# PT2258-S_Breakout.net
KiCad netlist of a schematic drawn in EAGLE
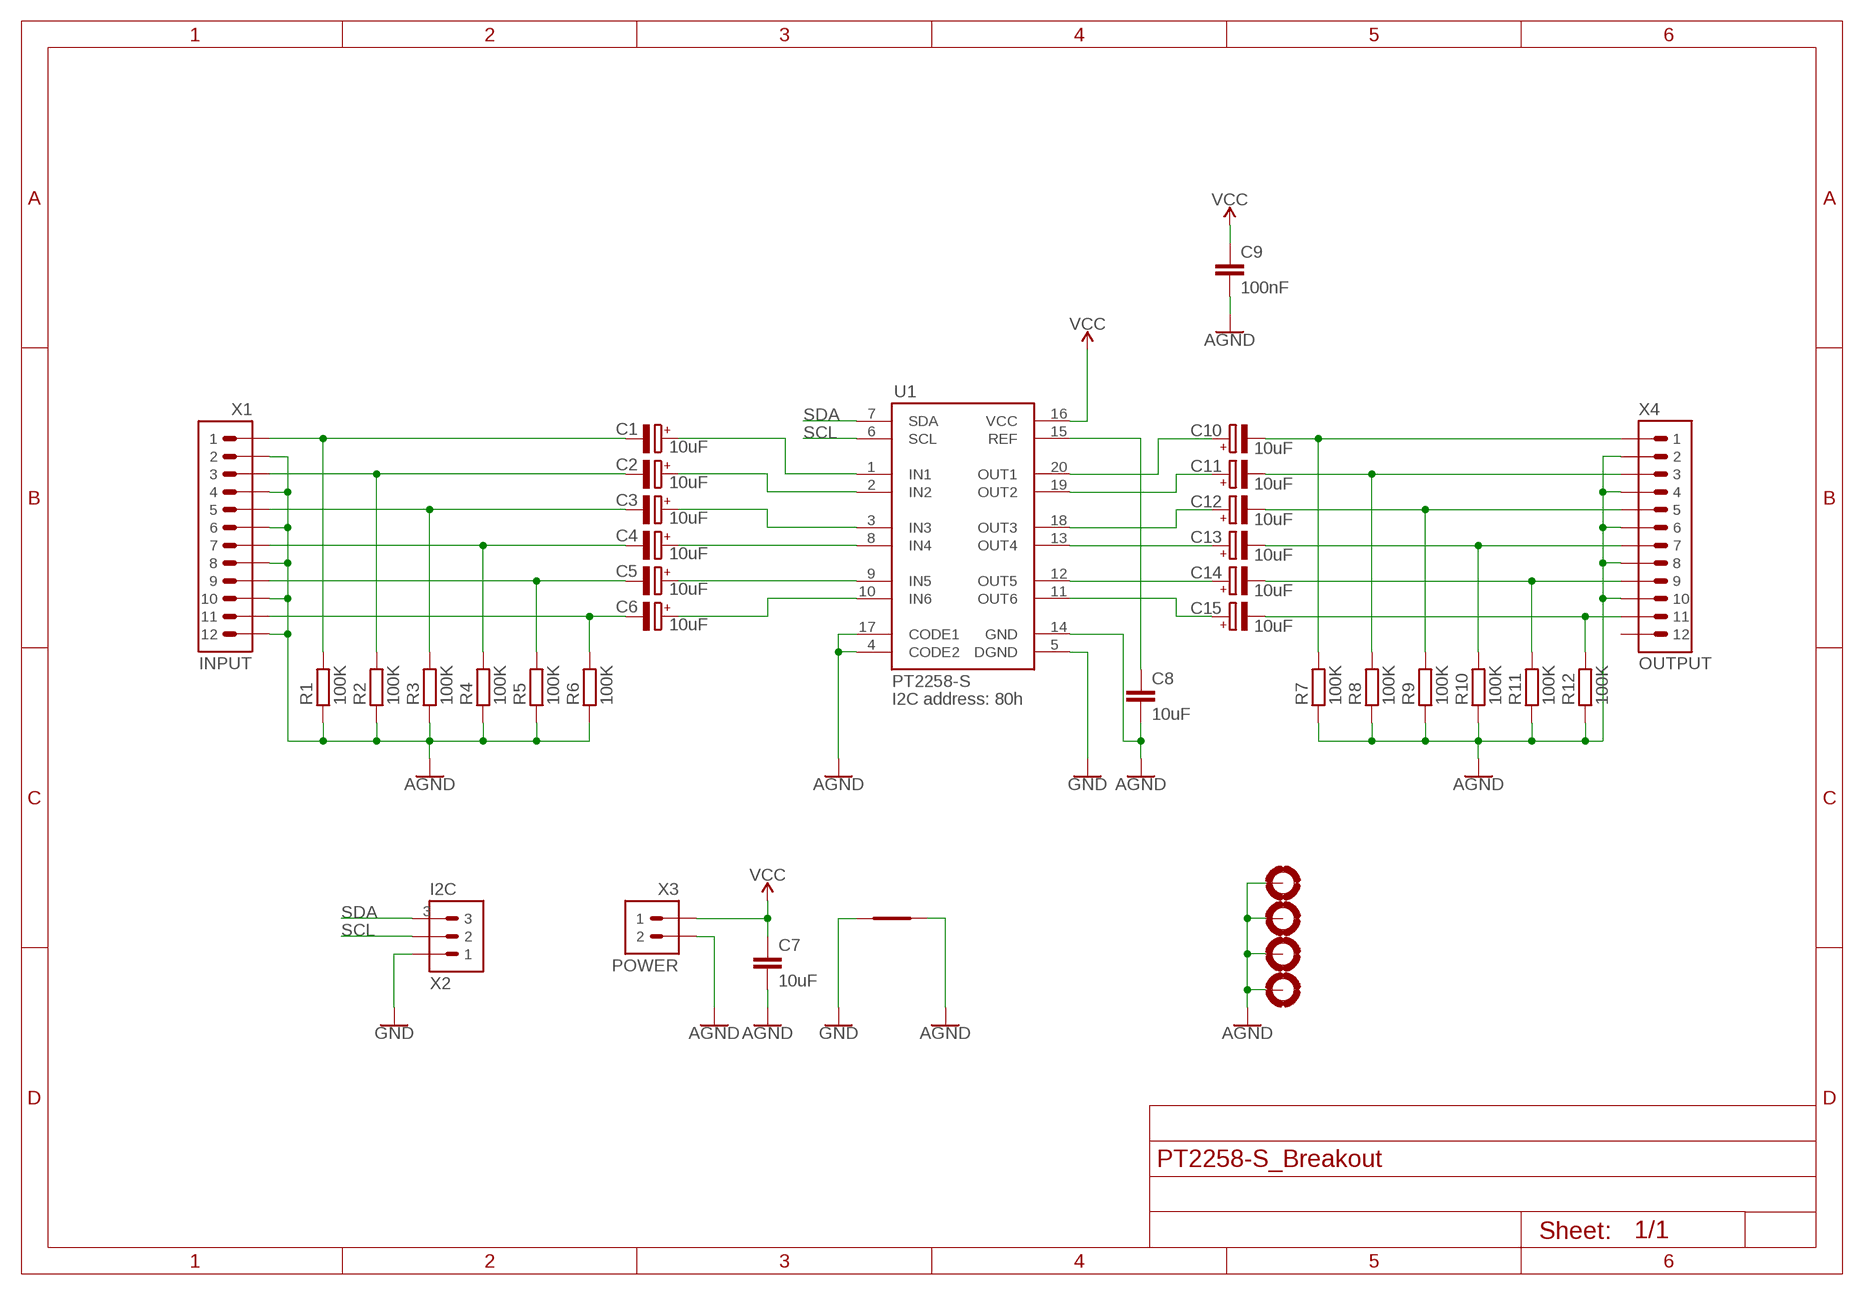
[diagram p0: schematic, sheet 1]

(export (version "E")
  (design (tool "Eeschema 10.0.6"))
  (components
    (comp (ref "C1")
      (value "10uF")
      (footprint "eagle-import:ROQANG-RVT0405")
      (libsource (lib "eagle-import") (part "CAP-POL-ALUMROQANG-RVT0405"))
    )
    (comp (ref "C2")
      (value "10uF")
      (footprint "eagle-import:ROQANG-RVT0405")
      (libsource (lib "eagle-import") (part "CAP-POL-ALUMROQANG-RVT0405"))
    )
    (comp (ref "C3")
      (value "10uF")
      (footprint "eagle-import:ROQANG-RVT0405")
      (libsource (lib "eagle-import") (part "CAP-POL-ALUMROQANG-RVT0405"))
    )
    (comp (ref "C4")
      (value "10uF")
      (footprint "eagle-import:ROQANG-RVT0405")
      (libsource (lib "eagle-import") (part "CAP-POL-ALUMROQANG-RVT0405"))
    )
    (comp (ref "C5")
      (value "10uF")
      (footprint "eagle-import:ROQANG-RVT0405")
      (libsource (lib "eagle-import") (part "CAP-POL-ALUMROQANG-RVT0405"))
    )
    (comp (ref "C6")
      (value "10uF")
      (footprint "eagle-import:ROQANG-RVT0405")
      (libsource (lib "eagle-import") (part "CAP-POL-ALUMROQANG-RVT0405"))
    )
    (comp (ref "C7")
      (value "10uF")
      (footprint "eagle-import:C0603")
      (libsource (lib "eagle-import") (part "CAPC0603"))
    )
    (comp (ref "C8")
      (value "10uF")
      (footprint "eagle-import:C0603")
      (libsource (lib "eagle-import") (part "CAPC0603"))
    )
    (comp (ref "C9")
      (value "100nF")
      (footprint "eagle-import:C0603")
      (libsource (lib "eagle-import") (part "CAPC0603"))
    )
    (comp (ref "C10")
      (value "10uF")
      (footprint "eagle-import:ROQANG-RVT0405")
      (libsource (lib "eagle-import") (part "CAP-POL-ALUMROQANG-RVT0405"))
    )
    (comp (ref "C11")
      (value "10uF")
      (footprint "eagle-import:ROQANG-RVT0405")
      (libsource (lib "eagle-import") (part "CAP-POL-ALUMROQANG-RVT0405"))
    )
    (comp (ref "C12")
      (value "10uF")
      (footprint "eagle-import:ROQANG-RVT0405")
      (libsource (lib "eagle-import") (part "CAP-POL-ALUMROQANG-RVT0405"))
    )
    (comp (ref "C13")
      (value "10uF")
      (footprint "eagle-import:ROQANG-RVT0405")
      (libsource (lib "eagle-import") (part "CAP-POL-ALUMROQANG-RVT0405"))
    )
    (comp (ref "C14")
      (value "10uF")
      (footprint "eagle-import:ROQANG-RVT0405")
      (libsource (lib "eagle-import") (part "CAP-POL-ALUMROQANG-RVT0405"))
    )
    (comp (ref "C15")
      (value "10uF")
      (footprint "eagle-import:ROQANG-RVT0405")
      (libsource (lib "eagle-import") (part "CAP-POL-ALUMROQANG-RVT0405"))
    )
    (comp (ref "H1")
      (value "MOUNTHOLE-PAD3.2")
      (footprint "eagle-import:3.2-PAD")
      (libsource (lib "eagle-import") (part "MOUNTHOLE-PAD3.2"))
    )
    (comp (ref "H2")
      (value "MOUNTHOLE-PAD3.2")
      (footprint "eagle-import:3.2-PAD")
      (libsource (lib "eagle-import") (part "MOUNTHOLE-PAD3.2"))
    )
    (comp (ref "H3")
      (value "MOUNTHOLE-PAD3.2")
      (footprint "eagle-import:3.2-PAD")
      (libsource (lib "eagle-import") (part "MOUNTHOLE-PAD3.2"))
    )
    (comp (ref "H4")
      (value "MOUNTHOLE-PAD3.2")
      (footprint "eagle-import:3.2-PAD")
      (libsource (lib "eagle-import") (part "MOUNTHOLE-PAD3.2"))
    )
    (comp (ref "R1")
      (value "100K")
      (footprint "eagle-import:R0603")
      (libsource (lib "eagle-import") (part "RESISTOR0603"))
    )
    (comp (ref "R2")
      (value "100K")
      (footprint "eagle-import:R0603")
      (libsource (lib "eagle-import") (part "RESISTOR0603"))
    )
    (comp (ref "R3")
      (value "100K")
      (footprint "eagle-import:R0603")
      (libsource (lib "eagle-import") (part "RESISTOR0603"))
    )
    (comp (ref "R4")
      (value "100K")
      (footprint "eagle-import:R0603")
      (libsource (lib "eagle-import") (part "RESISTOR0603"))
    )
    (comp (ref "R5")
      (value "100K")
      (footprint "eagle-import:R0603")
      (libsource (lib "eagle-import") (part "RESISTOR0603"))
    )
    (comp (ref "R6")
      (value "100K")
      (footprint "eagle-import:R0603")
      (libsource (lib "eagle-import") (part "RESISTOR0603"))
    )
    (comp (ref "R7")
      (value "100K")
      (footprint "eagle-import:R0603")
      (libsource (lib "eagle-import") (part "RESISTOR0603"))
    )
    (comp (ref "R8")
      (value "100K")
      (footprint "eagle-import:R0603")
      (libsource (lib "eagle-import") (part "RESISTOR0603"))
    )
    (comp (ref "R9")
      (value "100K")
      (footprint "eagle-import:R0603")
      (libsource (lib "eagle-import") (part "RESISTOR0603"))
    )
    (comp (ref "R10")
      (value "100K")
      (footprint "eagle-import:R0603")
      (libsource (lib "eagle-import") (part "RESISTOR0603"))
    )
    (comp (ref "R11")
      (value "100K")
      (footprint "eagle-import:R0603")
      (libsource (lib "eagle-import") (part "RESISTOR0603"))
    )
    (comp (ref "R12")
      (value "100K")
      (footprint "eagle-import:R0603")
      (libsource (lib "eagle-import") (part "RESISTOR0603"))
    )
    (comp (ref "SH1")
      (value "SHORT-SMD-06096")
      (footprint "eagle-import:SHORT-SMD-06096")
      (libsource (lib "eagle-import") (part "SHORT-SMD-06096"))
    )
    (comp (ref "U1")
      (value "PT2258-S")
      (footprint "eagle-import:SOP-20-300")
      (libsource (lib "eagle-import") (part "PT2258-S"))
    )
    (comp (ref "X1")
      (value "INPUT")
      (footprint "eagle-import:1X12-2.54")
      (libsource (lib "eagle-import") (part "HEADER-1X12-2.54"))
    )
    (comp (ref "X2")
      (value "I2C")
      (footprint "eagle-import:1X03P-2.54")
      (libsource (lib "eagle-import") (part "HEADER-1X03-2.54P"))
    )
    (comp (ref "X3")
      (value "POWER")
      (footprint "eagle-import:1X02P-2.54")
      (libsource (lib "eagle-import") (part "HEADER-1X02-2.54POL"))
    )
    (comp (ref "X4")
      (value "OUTPUT")
      (footprint "eagle-import:1X12-2.54")
      (libsource (lib "eagle-import") (part "HEADER-1X12-2.54"))
    )
  )
  (nets
    (net (code "1") (name "/SCL") (class "Default")
      (node (ref "U1") (pin "6") (pinfunction "SCL_6") (pintype "bidirectional"))
      (node (ref "X2") (pin "2") (pinfunction "2_2") (pintype "passive"))
    )
    (net (code "2") (name "/SDA") (class "Default")
      (node (ref "U1") (pin "7") (pinfunction "SDA_7") (pintype "bidirectional"))
      (node (ref "X2") (pin "3") (pinfunction "3_3") (pintype "passive"))
    )
    (net (code "3") (name "AGND") (class "Default")
      (node (ref "C7") (pin "2") (pinfunction "2_2") (pintype "passive"))
      (node (ref "C8") (pin "2") (pinfunction "2_2") (pintype "passive"))
      (node (ref "C9") (pin "2") (pinfunction "2_2") (pintype "passive"))
      (node (ref "H1") (pin "B3,2") (pinfunction "MOUNT_B3,2") (pintype "passive"))
      (node (ref "H2") (pin "B3,2") (pinfunction "MOUNT_B3,2") (pintype "passive"))
      (node (ref "H3") (pin "B3,2") (pinfunction "MOUNT_B3,2") (pintype "passive"))
      (node (ref "H4") (pin "B3,2") (pinfunction "MOUNT_B3,2") (pintype "passive"))
      (node (ref "R1") (pin "1") (pinfunction "1_1") (pintype "passive"))
      (node (ref "R10") (pin "1") (pinfunction "1_1") (pintype "passive"))
      (node (ref "R11") (pin "1") (pinfunction "1_1") (pintype "passive"))
      (node (ref "R12") (pin "1") (pinfunction "1_1") (pintype "passive"))
      (node (ref "R2") (pin "1") (pinfunction "1_1") (pintype "passive"))
      (node (ref "R3") (pin "1") (pinfunction "1_1") (pintype "passive"))
      (node (ref "R4") (pin "1") (pinfunction "1_1") (pintype "passive"))
      (node (ref "R5") (pin "1") (pinfunction "1_1") (pintype "passive"))
      (node (ref "R6") (pin "1") (pinfunction "1_1") (pintype "passive"))
      (node (ref "R7") (pin "1") (pinfunction "1_1") (pintype "passive"))
      (node (ref "R8") (pin "1") (pinfunction "1_1") (pintype "passive"))
      (node (ref "R9") (pin "1") (pinfunction "1_1") (pintype "passive"))
      (node (ref "SH1") (pin "2") (pinfunction "P$2_2") (pintype "bidirectional"))
      (node (ref "U1") (pin "14") (pinfunction "GND_14") (pintype "bidirectional"))
      (node (ref "U1") (pin "17") (pinfunction "CODE1_17") (pintype "bidirectional"))
      (node (ref "U1") (pin "4") (pinfunction "CODE2_4") (pintype "bidirectional"))
      (node (ref "X1") (pin "10") (pinfunction "10_10") (pintype "bidirectional"))
      (node (ref "X1") (pin "12") (pinfunction "12_12") (pintype "bidirectional"))
      (node (ref "X1") (pin "2") (pinfunction "2_2") (pintype "passive"))
      (node (ref "X1") (pin "4") (pinfunction "4_4") (pintype "passive"))
      (node (ref "X1") (pin "6") (pinfunction "6_6") (pintype "passive"))
      (node (ref "X1") (pin "8") (pinfunction "8_8") (pintype "bidirectional"))
      (node (ref "X3") (pin "2") (pinfunction "2_2") (pintype "passive"))
      (node (ref "X4") (pin "10") (pinfunction "10_10") (pintype "bidirectional"))
      (node (ref "X4") (pin "2") (pinfunction "2_2") (pintype "passive"))
      (node (ref "X4") (pin "4") (pinfunction "4_4") (pintype "passive"))
      (node (ref "X4") (pin "6") (pinfunction "6_6") (pintype "passive"))
      (node (ref "X4") (pin "8") (pinfunction "8_8") (pintype "bidirectional"))
    )
    (net (code "4") (name "GND") (class "Default")
      (node (ref "SH1") (pin "1") (pinfunction "P$1_1") (pintype "bidirectional"))
      (node (ref "U1") (pin "5") (pinfunction "DGND_5") (pintype "bidirectional"))
      (node (ref "X2") (pin "1") (pinfunction "1_1") (pintype "passive"))
    )
    (net (code "5") (name "Net-(C1-Pad-)") (class "Default")
      (node (ref "C1") (pin "-") (pinfunction "-_-") (pintype "passive"))
      (node (ref "R1") (pin "2") (pinfunction "2_2") (pintype "passive"))
      (node (ref "X1") (pin "1") (pinfunction "1_1") (pintype "passive"))
    )
    (net (code "6") (name "Net-(C2-Pad-)") (class "Default")
      (node (ref "C2") (pin "-") (pinfunction "-_-") (pintype "passive"))
      (node (ref "R2") (pin "2") (pinfunction "2_2") (pintype "passive"))
      (node (ref "X1") (pin "3") (pinfunction "3_3") (pintype "passive"))
    )
    (net (code "7") (name "Net-(C3-Pad-)") (class "Default")
      (node (ref "C3") (pin "-") (pinfunction "-_-") (pintype "passive"))
      (node (ref "R3") (pin "2") (pinfunction "2_2") (pintype "passive"))
      (node (ref "X1") (pin "5") (pinfunction "5_5") (pintype "passive"))
    )
    (net (code "8") (name "Net-(C4-Pad-)") (class "Default")
      (node (ref "C4") (pin "-") (pinfunction "-_-") (pintype "passive"))
      (node (ref "R4") (pin "2") (pinfunction "2_2") (pintype "passive"))
      (node (ref "X1") (pin "7") (pinfunction "7_7") (pintype "passive"))
    )
    (net (code "9") (name "Net-(C5-Pad-)") (class "Default")
      (node (ref "C5") (pin "-") (pinfunction "-_-") (pintype "passive"))
      (node (ref "R5") (pin "2") (pinfunction "2_2") (pintype "passive"))
      (node (ref "X1") (pin "9") (pinfunction "9_9") (pintype "bidirectional"))
    )
    (net (code "10") (name "Net-(C6-Pad-)") (class "Default")
      (node (ref "C6") (pin "-") (pinfunction "-_-") (pintype "passive"))
      (node (ref "R6") (pin "2") (pinfunction "2_2") (pintype "passive"))
      (node (ref "X1") (pin "11") (pinfunction "11_11") (pintype "bidirectional"))
    )
    (net (code "11") (name "Net-(C10-Pad-)") (class "Default")
      (node (ref "C10") (pin "-") (pinfunction "-_-") (pintype "passive"))
      (node (ref "R7") (pin "2") (pinfunction "2_2") (pintype "passive"))
      (node (ref "X4") (pin "1") (pinfunction "1_1") (pintype "passive"))
    )
    (net (code "12") (name "Net-(C11-Pad-)") (class "Default")
      (node (ref "C11") (pin "-") (pinfunction "-_-") (pintype "passive"))
      (node (ref "R8") (pin "2") (pinfunction "2_2") (pintype "passive"))
      (node (ref "X4") (pin "3") (pinfunction "3_3") (pintype "passive"))
    )
    (net (code "13") (name "Net-(C12-Pad-)") (class "Default")
      (node (ref "C12") (pin "-") (pinfunction "-_-") (pintype "passive"))
      (node (ref "R9") (pin "2") (pinfunction "2_2") (pintype "passive"))
      (node (ref "X4") (pin "5") (pinfunction "5_5") (pintype "passive"))
    )
    (net (code "14") (name "Net-(C13-Pad-)") (class "Default")
      (node (ref "C13") (pin "-") (pinfunction "-_-") (pintype "passive"))
      (node (ref "R10") (pin "2") (pinfunction "2_2") (pintype "passive"))
      (node (ref "X4") (pin "7") (pinfunction "7_7") (pintype "passive"))
    )
    (net (code "15") (name "Net-(C14-Pad-)") (class "Default")
      (node (ref "C14") (pin "-") (pinfunction "-_-") (pintype "passive"))
      (node (ref "R11") (pin "2") (pinfunction "2_2") (pintype "passive"))
      (node (ref "X4") (pin "9") (pinfunction "9_9") (pintype "bidirectional"))
    )
    (net (code "16") (name "Net-(C15-Pad-)") (class "Default")
      (node (ref "C15") (pin "-") (pinfunction "-_-") (pintype "passive"))
      (node (ref "R12") (pin "2") (pinfunction "2_2") (pintype "passive"))
      (node (ref "X4") (pin "11") (pinfunction "11_11") (pintype "bidirectional"))
    )
    (net (code "17") (name "Net-(U1-IN1)") (class "Default")
      (node (ref "C1") (pin "+") (pinfunction "+_+") (pintype "passive"))
      (node (ref "U1") (pin "1") (pinfunction "IN1_1") (pintype "bidirectional"))
    )
    (net (code "18") (name "Net-(U1-IN2)") (class "Default")
      (node (ref "C2") (pin "+") (pinfunction "+_+") (pintype "passive"))
      (node (ref "U1") (pin "2") (pinfunction "IN2_2") (pintype "bidirectional"))
    )
    (net (code "19") (name "Net-(U1-IN3)") (class "Default")
      (node (ref "C3") (pin "+") (pinfunction "+_+") (pintype "passive"))
      (node (ref "U1") (pin "3") (pinfunction "IN3_3") (pintype "bidirectional"))
    )
    (net (code "20") (name "Net-(U1-IN4)") (class "Default")
      (node (ref "C4") (pin "+") (pinfunction "+_+") (pintype "passive"))
      (node (ref "U1") (pin "8") (pinfunction "IN4_8") (pintype "bidirectional"))
    )
    (net (code "21") (name "Net-(U1-IN5)") (class "Default")
      (node (ref "C5") (pin "+") (pinfunction "+_+") (pintype "passive"))
      (node (ref "U1") (pin "9") (pinfunction "IN5_9") (pintype "bidirectional"))
    )
    (net (code "22") (name "Net-(U1-IN6)") (class "Default")
      (node (ref "C6") (pin "+") (pinfunction "+_+") (pintype "passive"))
      (node (ref "U1") (pin "10") (pinfunction "IN6_10") (pintype "bidirectional"))
    )
    (net (code "23") (name "Net-(U1-OUT1)") (class "Default")
      (node (ref "C10") (pin "+") (pinfunction "+_+") (pintype "passive"))
      (node (ref "U1") (pin "20") (pinfunction "OUT1_20") (pintype "bidirectional"))
    )
    (net (code "24") (name "Net-(U1-OUT2)") (class "Default")
      (node (ref "C11") (pin "+") (pinfunction "+_+") (pintype "passive"))
      (node (ref "U1") (pin "19") (pinfunction "OUT2_19") (pintype "bidirectional"))
    )
    (net (code "25") (name "Net-(U1-OUT3)") (class "Default")
      (node (ref "C12") (pin "+") (pinfunction "+_+") (pintype "passive"))
      (node (ref "U1") (pin "18") (pinfunction "OUT3_18") (pintype "bidirectional"))
    )
    (net (code "26") (name "Net-(U1-OUT4)") (class "Default")
      (node (ref "C13") (pin "+") (pinfunction "+_+") (pintype "passive"))
      (node (ref "U1") (pin "13") (pinfunction "OUT4_13") (pintype "bidirectional"))
    )
    (net (code "27") (name "Net-(U1-OUT5)") (class "Default")
      (node (ref "C14") (pin "+") (pinfunction "+_+") (pintype "passive"))
      (node (ref "U1") (pin "12") (pinfunction "OUT5_12") (pintype "bidirectional"))
    )
    (net (code "28") (name "Net-(U1-OUT6)") (class "Default")
      (node (ref "C15") (pin "+") (pinfunction "+_+") (pintype "passive"))
      (node (ref "U1") (pin "11") (pinfunction "OUT6_11") (pintype "bidirectional"))
    )
    (net (code "29") (name "Net-(U1-REF)") (class "Default")
      (node (ref "C8") (pin "1") (pinfunction "1_1") (pintype "passive"))
      (node (ref "U1") (pin "15") (pinfunction "REF_15") (pintype "bidirectional"))
    )
    (net (code "30") (name "VCC") (class "Default")
      (node (ref "C7") (pin "1") (pinfunction "1_1") (pintype "passive"))
      (node (ref "C9") (pin "1") (pinfunction "1_1") (pintype "passive"))
      (node (ref "U1") (pin "16") (pinfunction "VCC_16") (pintype "bidirectional"))
      (node (ref "X3") (pin "1") (pinfunction "1_1") (pintype "passive"))
    )
    (net (code "31") (name "unconnected-(X4-Pad12)") (class "Default")
      (node (ref "X4") (pin "12") (pinfunction "12_12") (pintype "bidirectional"))
    )
  )
)
